# PM_proto_5.net
KiCad netlist of a schematic drawn in EAGLE
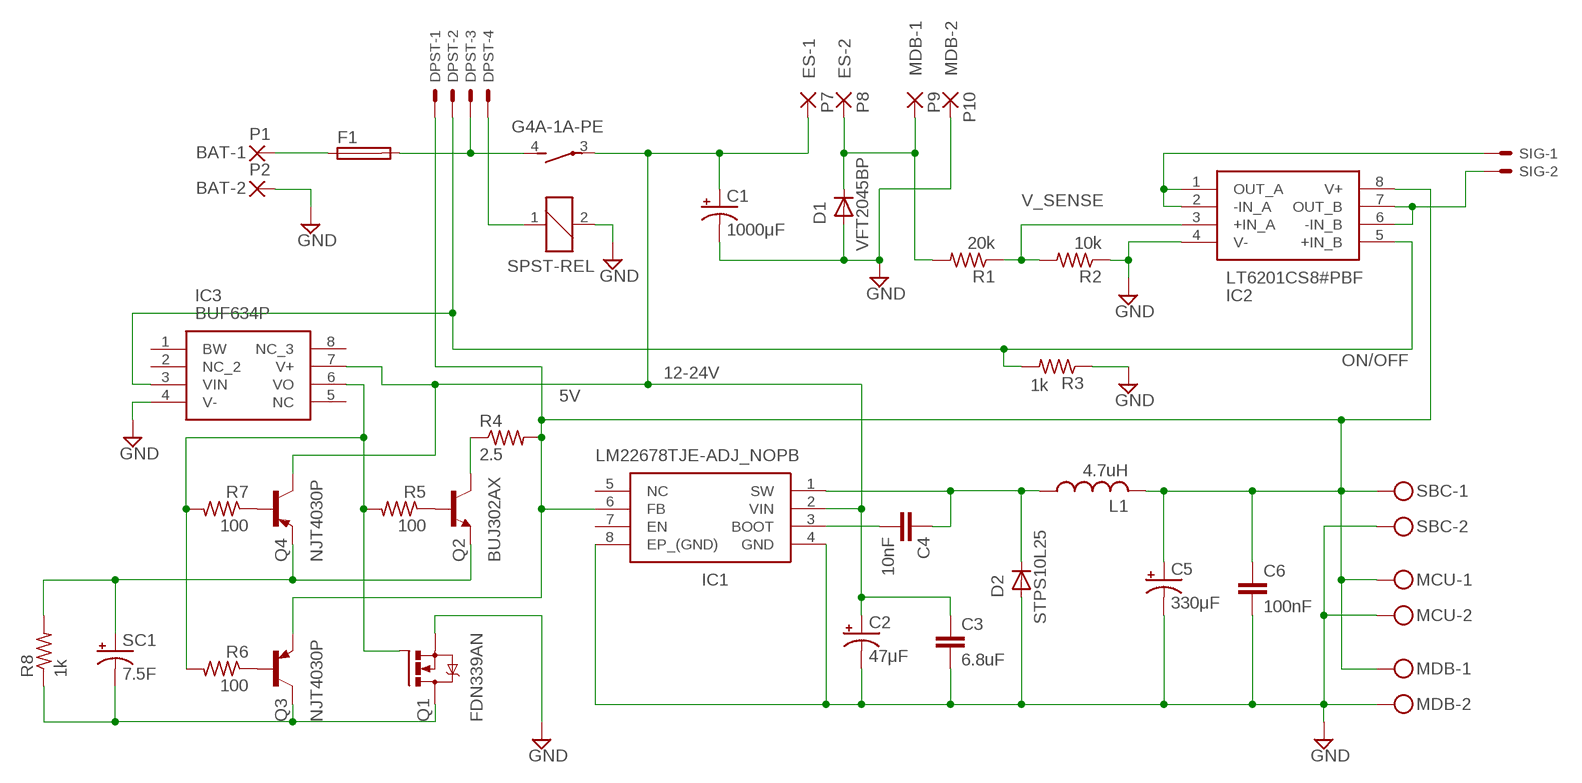
[diagram p0: schematic, sheet 1]

(export (version "E")
  (design (tool "Eeschema 10.0.6"))
  (components
    (comp (ref "C1")
      (value "1000μF")
      (footprint "eagle-import:E7,5-16")
      (libsource (lib "eagle-import") (part "CPOL-USE7.5-16"))
    )
    (comp (ref "C2")
      (value "47μF")
      (footprint "eagle-import:E2,5-6E")
      (libsource (lib "eagle-import") (part "CPOL-USE2,5-6E"))
    )
    (comp (ref "C3")
      (value "6.8uF")
      (footprint "eagle-import:C025-024X044")
      (libsource (lib "eagle-import") (part "C-EU025-024X044"))
    )
    (comp (ref "C4")
      (value "10nF")
      (footprint "eagle-import:C025-024X044")
      (libsource (lib "eagle-import") (part "C-EU025-024X044"))
    )
    (comp (ref "C5")
      (value "330μF")
      (footprint "eagle-import:E2,5-6E")
      (libsource (lib "eagle-import") (part "CPOL-USE2,5-6E"))
    )
    (comp (ref "C6")
      (value "100nF")
      (footprint "eagle-import:C025-024X044")
      (libsource (lib "eagle-import") (part "C-EU025-024X044"))
    )
    (comp (ref "D1")
      (value "VFT2045BP")
      (footprint "eagle-import:VFT2045BP")
      (libsource (lib "eagle-import") (part "VFT2045BP"))
    )
    (comp (ref "D2")
      (value "STPS10L25")
      (footprint "eagle-import:VFT2045BP")
      (libsource (lib "eagle-import") (part "VFT2045BP"))
    )
    (comp (ref "DPST")
      (value "JST-XH-04-PIN-LONG-PAD")
      (footprint "eagle-import:JST-XH-04-PACKAGE-LONG-PAD")
      (libsource (lib "eagle-import") (part "JST-XH-04-PIN-LONG-PAD"))
    )
    (comp (ref "F1")
      (value "0297015FUSE")
      (footprint "eagle-import:0297015HOLDER")
      (libsource (lib "eagle-import") (part "0297015FUSE"))
    )
    (comp (ref "IC1")
      (value "LM22678TJE-ADJ_NOPB")
      (footprint "eagle-import:LM22678TJEADJNOPB")
      (fields
        (field (name "ARROW_PART_NUMBER") "LM22678TJE-ADJ/NOPB")
        (field (name "RS_PART_NUMBER") "1625056")
      )
      (libsource (lib "eagle-import") (part "LM22678TJE-ADJ_NOPB"))
    )
    (comp (ref "IC2")
      (value "LT6201CS8#PBF")
      (footprint "eagle-import:SOIC127P599X175-8N")
      (fields (field (name "RS_PART_NUMBER") "5061072P"))
      (libsource (lib "eagle-import") (part "LT6201CS8#PBF"))
    )
    (comp (ref "IC3")
      (value "BUF634P")
      (footprint "eagle-import:DIP254P762X508-8")
      (fields (field (name "RS_PART_NUMBER") "6604217P"))
      (libsource (lib "eagle-import") (part "BUF634P"))
    )
    (comp (ref "L1")
      (value "4.7uH")
      (footprint "eagle-import:6000-XXXX-RC")
      (libsource (lib "eagle-import") (part "L-US6000-XXX-RC"))
    )
    (comp (ref "MCU")
      (value "MKDSN1,5/2-5,08")
      (footprint "eagle-import:MKDSN1,5_2-5,08")
      (libsource (lib "eagle-import") (part "MKDSN1,5/2-5,08"))
    )
    (comp (ref "MDB")
      (value "MKDSN1,5/2-5,08")
      (footprint "eagle-import:MKDSN1,5_2-5,08")
      (libsource (lib "eagle-import") (part "MKDSN1,5/2-5,08"))
    )
    (comp (ref "P1")
      (value "BAT-1")
      (footprint "eagle-import:1,6_0,8")
      (libsource (lib "eagle-import") (part "1,6/0,8"))
    )
    (comp (ref "P2")
      (value "BAT-2")
      (footprint "eagle-import:1,6_0,8")
      (libsource (lib "eagle-import") (part "1,6/0,8"))
    )
    (comp (ref "P7")
      (value "ES-1")
      (footprint "eagle-import:1,6_0,8")
      (libsource (lib "eagle-import") (part "1,6/0,8"))
    )
    (comp (ref "P8")
      (value "ES-2")
      (footprint "eagle-import:1,6_0,8")
      (libsource (lib "eagle-import") (part "1,6/0,8"))
    )
    (comp (ref "P9")
      (value "MDB-1")
      (footprint "eagle-import:1,6_0,8")
      (libsource (lib "eagle-import") (part "1,6/0,8"))
    )
    (comp (ref "P10")
      (value "MDB-2")
      (footprint "eagle-import:1,6_0,8")
      (libsource (lib "eagle-import") (part "1,6/0,8"))
    )
    (comp (ref "Q1")
      (value "FDN339AN")
      (footprint "eagle-import:TO220BH")
      (libsource (lib "eagle-import") (part "IRFZ48Z"))
    )
    (comp (ref "Q2")
      (value "BUJ302AX")
      (footprint "eagle-import:TO18")
      (libsource (lib "eagle-import") (part "2N706"))
    )
    (comp (ref "Q3")
      (value "NJT4030P")
      (footprint "eagle-import:TO18")
      (libsource (lib "eagle-import") (part "-PNP-TO18-EBCBC177B"))
    )
    (comp (ref "Q4")
      (value "NJT4030P")
      (footprint "eagle-import:TO18")
      (libsource (lib "eagle-import") (part "-PNP-TO18-EBCBC177B"))
    )
    (comp (ref "R1")
      (value "20k")
      (footprint "eagle-import:0204_7")
      (libsource (lib "eagle-import") (part "R-US_0204/7"))
    )
    (comp (ref "R2")
      (value "10k")
      (footprint "eagle-import:0204_7")
      (libsource (lib "eagle-import") (part "R-US_0204/7"))
    )
    (comp (ref "R3")
      (value "1k")
      (footprint "eagle-import:0204_7")
      (libsource (lib "eagle-import") (part "R-US_0204/7"))
    )
    (comp (ref "R4")
      (value "2.5")
      (footprint "eagle-import:TNP10SC10R0FE")
      (libsource (lib "eagle-import") (part "TNP10SC10R0FE"))
    )
    (comp (ref "R5")
      (value "100")
      (footprint "eagle-import:0204_7")
      (libsource (lib "eagle-import") (part "R-US_0204/7"))
    )
    (comp (ref "R6")
      (value "100")
      (footprint "eagle-import:0204_7")
      (libsource (lib "eagle-import") (part "R-US_0204/7"))
    )
    (comp (ref "R7")
      (value "100")
      (footprint "eagle-import:0204_7")
      (libsource (lib "eagle-import") (part "R-US_0204/7"))
    )
    (comp (ref "R8")
      (value "1k")
      (footprint "eagle-import:0204_7")
      (libsource (lib "eagle-import") (part "R-US_0204/7"))
    )
    (comp (ref "SBC")
      (value "MKDSN1,5/2-5,08")
      (footprint "eagle-import:MKDSN1,5_2-5,08")
      (libsource (lib "eagle-import") (part "MKDSN1,5/2-5,08"))
    )
    (comp (ref "SC1")
      (value "7.5F")
      (footprint "eagle-import:SCMT32D755MRBB0")
      (libsource (lib "eagle-import") (part "SCMT32D755MRBB0"))
    )
    (comp (ref "SIG")
      (value "JST-XH-02-PIN-LONG-PAD")
      (footprint "eagle-import:JST-XH-02-PACKAGE-LONG-PAD")
      (libsource (lib "eagle-import") (part "JST-XH-02-PIN-LONG-PAD"))
    )
    (comp (ref "SPST-REL")
      (value "G4A-1A-PE")
      (footprint "eagle-import:G4A-1A-PE")
      (libsource (lib "eagle-import") (part "G4A-1A-PE"))
    )
  )
  (nets
    (net (code "1") (name "/5V") (class "Default")
      (node (ref "C5") (pin "+") (pinfunction "+_+") (pintype "passive"))
      (node (ref "C6") (pin "1") (pinfunction "1_1") (pintype "passive"))
      (node (ref "DPST") (pin "1") (pinfunction "S_1") (pintype "passive"))
      (node (ref "IC1") (pin "6") (pinfunction "FB_6") (pintype "input"))
      (node (ref "IC2") (pin "8") (pinfunction "V+_8") (pintype "power_in"))
      (node (ref "L1") (pin "2") (pinfunction "2_2") (pintype "passive"))
      (node (ref "MCU") (pin "1") (pinfunction "KL_1") (pintype "passive"))
      (node (ref "MDB") (pin "1") (pinfunction "KL_1") (pintype "passive"))
      (node (ref "Q3") (pin "1") (pinfunction "E_1") (pintype "passive"))
      (node (ref "R4") (pin "2") (pinfunction "2_2") (pintype "passive"))
      (node (ref "SBC") (pin "1") (pinfunction "KL_1") (pintype "passive"))
    )
    (net (code "2") (name "/12-24V") (class "Default")
      (node (ref "C1") (pin "+") (pinfunction "+_+") (pintype "passive"))
      (node (ref "C2") (pin "+") (pinfunction "+_+") (pintype "passive"))
      (node (ref "C3") (pin "1") (pinfunction "1_1") (pintype "passive"))
      (node (ref "IC1") (pin "2") (pinfunction "VIN_2") (pintype "power_in"))
      (node (ref "IC3") (pin "7") (pinfunction "V+_7") (pintype "bidirectional"))
      (node (ref "P7") (pin "1") (pinfunction "P_1") (pintype "passive"))
      (node (ref "Q4") (pin "3") (pinfunction "C_3") (pintype "passive"))
      (node (ref "SPST-REL") (pin "3") (pinfunction "P_3") (pintype "passive"))
    )
    (net (code "3") (name "/ON{slash}OFF") (class "Default")
      (node (ref "DPST") (pin "2") (pinfunction "S_2") (pintype "passive"))
      (node (ref "IC2") (pin "5") (pinfunction "+IN_B_5") (pintype "input"))
      (node (ref "IC3") (pin "3") (pinfunction "VIN_3") (pintype "bidirectional"))
      (node (ref "R3") (pin "2") (pinfunction "2_2") (pintype "passive"))
    )
    (net (code "4") (name "/V_SENSE") (class "Default")
      (node (ref "IC2") (pin "3") (pinfunction "+IN_A_3") (pintype "input"))
      (node (ref "R1") (pin "1") (pinfunction "1_1") (pintype "passive"))
      (node (ref "R2") (pin "2") (pinfunction "2_2") (pintype "passive"))
    )
    (net (code "5") (name "GND") (class "Default")
      (node (ref "C1") (pin "-") (pinfunction "-_-") (pintype "passive"))
      (node (ref "C2") (pin "-") (pinfunction "-_-") (pintype "passive"))
      (node (ref "C3") (pin "2") (pinfunction "2_2") (pintype "passive"))
      (node (ref "C5") (pin "-") (pinfunction "-_-") (pintype "passive"))
      (node (ref "C6") (pin "2") (pinfunction "2_2") (pintype "passive"))
      (node (ref "D1") (pin "2") (pinfunction "A_2") (pintype "passive"))
      (node (ref "D2") (pin "2") (pinfunction "A_2") (pintype "passive"))
      (node (ref "IC1") (pin "4") (pinfunction "GND_4") (pintype "power_in"))
      (node (ref "IC1") (pin "8") (pinfunction "EP_(GND)_8") (pintype "power_in"))
      (node (ref "IC2") (pin "4") (pinfunction "V-_4") (pintype "power_in"))
      (node (ref "IC3") (pin "4") (pinfunction "V-_4") (pintype "bidirectional"))
      (node (ref "MCU") (pin "2") (pinfunction "KL_2") (pintype "passive"))
      (node (ref "MDB") (pin "2") (pinfunction "KL_2") (pintype "passive"))
      (node (ref "P10") (pin "1") (pinfunction "P_1") (pintype "passive"))
      (node (ref "P2") (pin "1") (pinfunction "P_1") (pintype "passive"))
      (node (ref "Q1") (pin "S") (pinfunction "S_S") (pintype "passive"))
      (node (ref "R2") (pin "1") (pinfunction "1_1") (pintype "passive"))
      (node (ref "R3") (pin "1") (pinfunction "1_1") (pintype "passive"))
      (node (ref "SBC") (pin "2") (pinfunction "KL_2") (pintype "passive"))
      (node (ref "SPST-REL") (pin "2") (pinfunction "2_2") (pintype "passive"))
    )
    (net (code "6") (name "Net-(D1-C)") (class "Default")
      (node (ref "D1") (pin "1") (pinfunction "C_1") (pintype "passive"))
      (node (ref "P8") (pin "1") (pinfunction "P_1") (pintype "passive"))
      (node (ref "P9") (pin "1") (pinfunction "P_1") (pintype "passive"))
      (node (ref "R1") (pin "2") (pinfunction "2_2") (pintype "passive"))
    )
    (net (code "7") (name "Net-(D2-C)") (class "Default")
      (node (ref "C4") (pin "1") (pinfunction "1_1") (pintype "passive"))
      (node (ref "D2") (pin "1") (pinfunction "C_1") (pintype "passive"))
      (node (ref "IC1") (pin "1") (pinfunction "SW_1") (pintype "power_in"))
      (node (ref "L1") (pin "1") (pinfunction "1_1") (pintype "passive"))
    )
    (net (code "8") (name "Net-(DPSTC-S)") (class "Default")
      (node (ref "DPST") (pin "3") (pinfunction "S_3") (pintype "passive"))
      (node (ref "F1") (pin "3") (pinfunction "2_3") (pintype "passive"))
      (node (ref "F1") (pin "4") (pinfunction "2_4") (pintype "passive"))
      (node (ref "SPST-REL") (pin "4") (pinfunction "S_4") (pintype "passive"))
    )
    (net (code "9") (name "Net-(DPSTD-S)") (class "Default")
      (node (ref "DPST") (pin "4") (pinfunction "S_4") (pintype "passive"))
      (node (ref "SPST-REL") (pin "1") (pinfunction "1_1") (pintype "passive"))
    )
    (net (code "10") (name "Net-(IC1-BOOT)") (class "Default")
      (node (ref "C4") (pin "2") (pinfunction "2_2") (pintype "passive"))
      (node (ref "IC1") (pin "3") (pinfunction "BOOT_3") (pintype "bidirectional"))
    )
    (net (code "11") (name "Net-(IC2--IN_A)") (class "Default")
      (node (ref "IC2") (pin "1") (pinfunction "OUT_A_1") (pintype "output"))
      (node (ref "IC2") (pin "2") (pinfunction "-IN_A_2") (pintype "input"))
      (node (ref "SIG") (pin "1") (pinfunction "S_1") (pintype "passive"))
    )
    (net (code "12") (name "Net-(IC2--IN_B)") (class "Default")
      (node (ref "IC2") (pin "6") (pinfunction "-IN_B_6") (pintype "input"))
      (node (ref "IC2") (pin "7") (pinfunction "OUT_B_7") (pintype "output"))
      (node (ref "SIG") (pin "2") (pinfunction "S_2") (pintype "passive"))
    )
    (net (code "13") (name "Net-(IC3-VO)") (class "Default")
      (node (ref "IC3") (pin "6") (pinfunction "VO_6") (pintype "bidirectional"))
      (node (ref "Q1") (pin "G") (pinfunction "G_G") (pintype "passive"))
      (node (ref "R5") (pin "2") (pinfunction "2_2") (pintype "passive"))
      (node (ref "R6") (pin "2") (pinfunction "2_2") (pintype "passive"))
      (node (ref "R7") (pin "2") (pinfunction "2_2") (pintype "passive"))
    )
    (net (code "14") (name "Net-(P1-P)") (class "Default")
      (node (ref "F1") (pin "1") (pinfunction "1_1") (pintype "passive"))
      (node (ref "F1") (pin "2") (pinfunction "1_2") (pintype "passive"))
      (node (ref "P1") (pin "1") (pinfunction "P_1") (pintype "passive"))
    )
    (net (code "15") (name "Net-(Q2-B)") (class "Default")
      (node (ref "Q2") (pin "2") (pinfunction "B_2") (pintype "passive"))
      (node (ref "R5") (pin "1") (pinfunction "1_1") (pintype "passive"))
    )
    (net (code "16") (name "Net-(Q2-C)") (class "Default")
      (node (ref "Q2") (pin "3") (pinfunction "C_3") (pintype "passive"))
      (node (ref "R4") (pin "1") (pinfunction "1_1") (pintype "passive"))
    )
    (net (code "17") (name "Net-(Q2-E)") (class "Default")
      (node (ref "Q2") (pin "1") (pinfunction "E_1") (pintype "passive"))
      (node (ref "Q4") (pin "1") (pinfunction "E_1") (pintype "passive"))
      (node (ref "R8") (pin "2") (pinfunction "2_2") (pintype "passive"))
      (node (ref "SC1") (pin "1") (pinfunction "+_1") (pintype "passive"))
    )
    (net (code "18") (name "Net-(Q3-B)") (class "Default")
      (node (ref "Q3") (pin "2") (pinfunction "B_2") (pintype "passive"))
      (node (ref "R6") (pin "1") (pinfunction "1_1") (pintype "passive"))
    )
    (net (code "19") (name "Net-(Q3-C)") (class "Default")
      (node (ref "Q1") (pin "D") (pinfunction "D_D") (pintype "passive"))
      (node (ref "Q3") (pin "3") (pinfunction "C_3") (pintype "passive"))
      (node (ref "R8") (pin "1") (pinfunction "1_1") (pintype "passive"))
      (node (ref "SC1") (pin "2") (pinfunction "-_2") (pintype "passive"))
    )
    (net (code "20") (name "Net-(Q4-B)") (class "Default")
      (node (ref "Q4") (pin "2") (pinfunction "B_2") (pintype "passive"))
      (node (ref "R7") (pin "1") (pinfunction "1_1") (pintype "passive"))
    )
    (net (code "21") (name "unconnected-(IC1-EN-Pad7)") (class "Default")
      (node (ref "IC1") (pin "7") (pinfunction "EN_7") (pintype "input"))
    )
    (net (code "22") (name "unconnected-(IC1-NC-Pad5)") (class "Default")
      (node (ref "IC1") (pin "5") (pinfunction "NC_5") (pintype "no_connect"))
    )
    (net (code "23") (name "unconnected-(IC3-BW-Pad1)") (class "Default")
      (node (ref "IC3") (pin "1") (pinfunction "BW_1") (pintype "bidirectional"))
    )
    (net (code "24") (name "unconnected-(IC3-NC-Pad5)") (class "Default")
      (node (ref "IC3") (pin "5") (pinfunction "NC_5") (pintype "no_connect"))
    )
    (net (code "25") (name "unconnected-(IC3-NC_2-Pad2)") (class "Default")
      (node (ref "IC3") (pin "2") (pinfunction "NC_2_2") (pintype "bidirectional"))
    )
    (net (code "26") (name "unconnected-(IC3-NC_3-Pad8)") (class "Default")
      (node (ref "IC3") (pin "8") (pinfunction "NC_3_8") (pintype "bidirectional"))
    )
  )
)
